# Git_USB_Hub.net
KiCad netlist of a schematic drawn in EasyEDA Pro
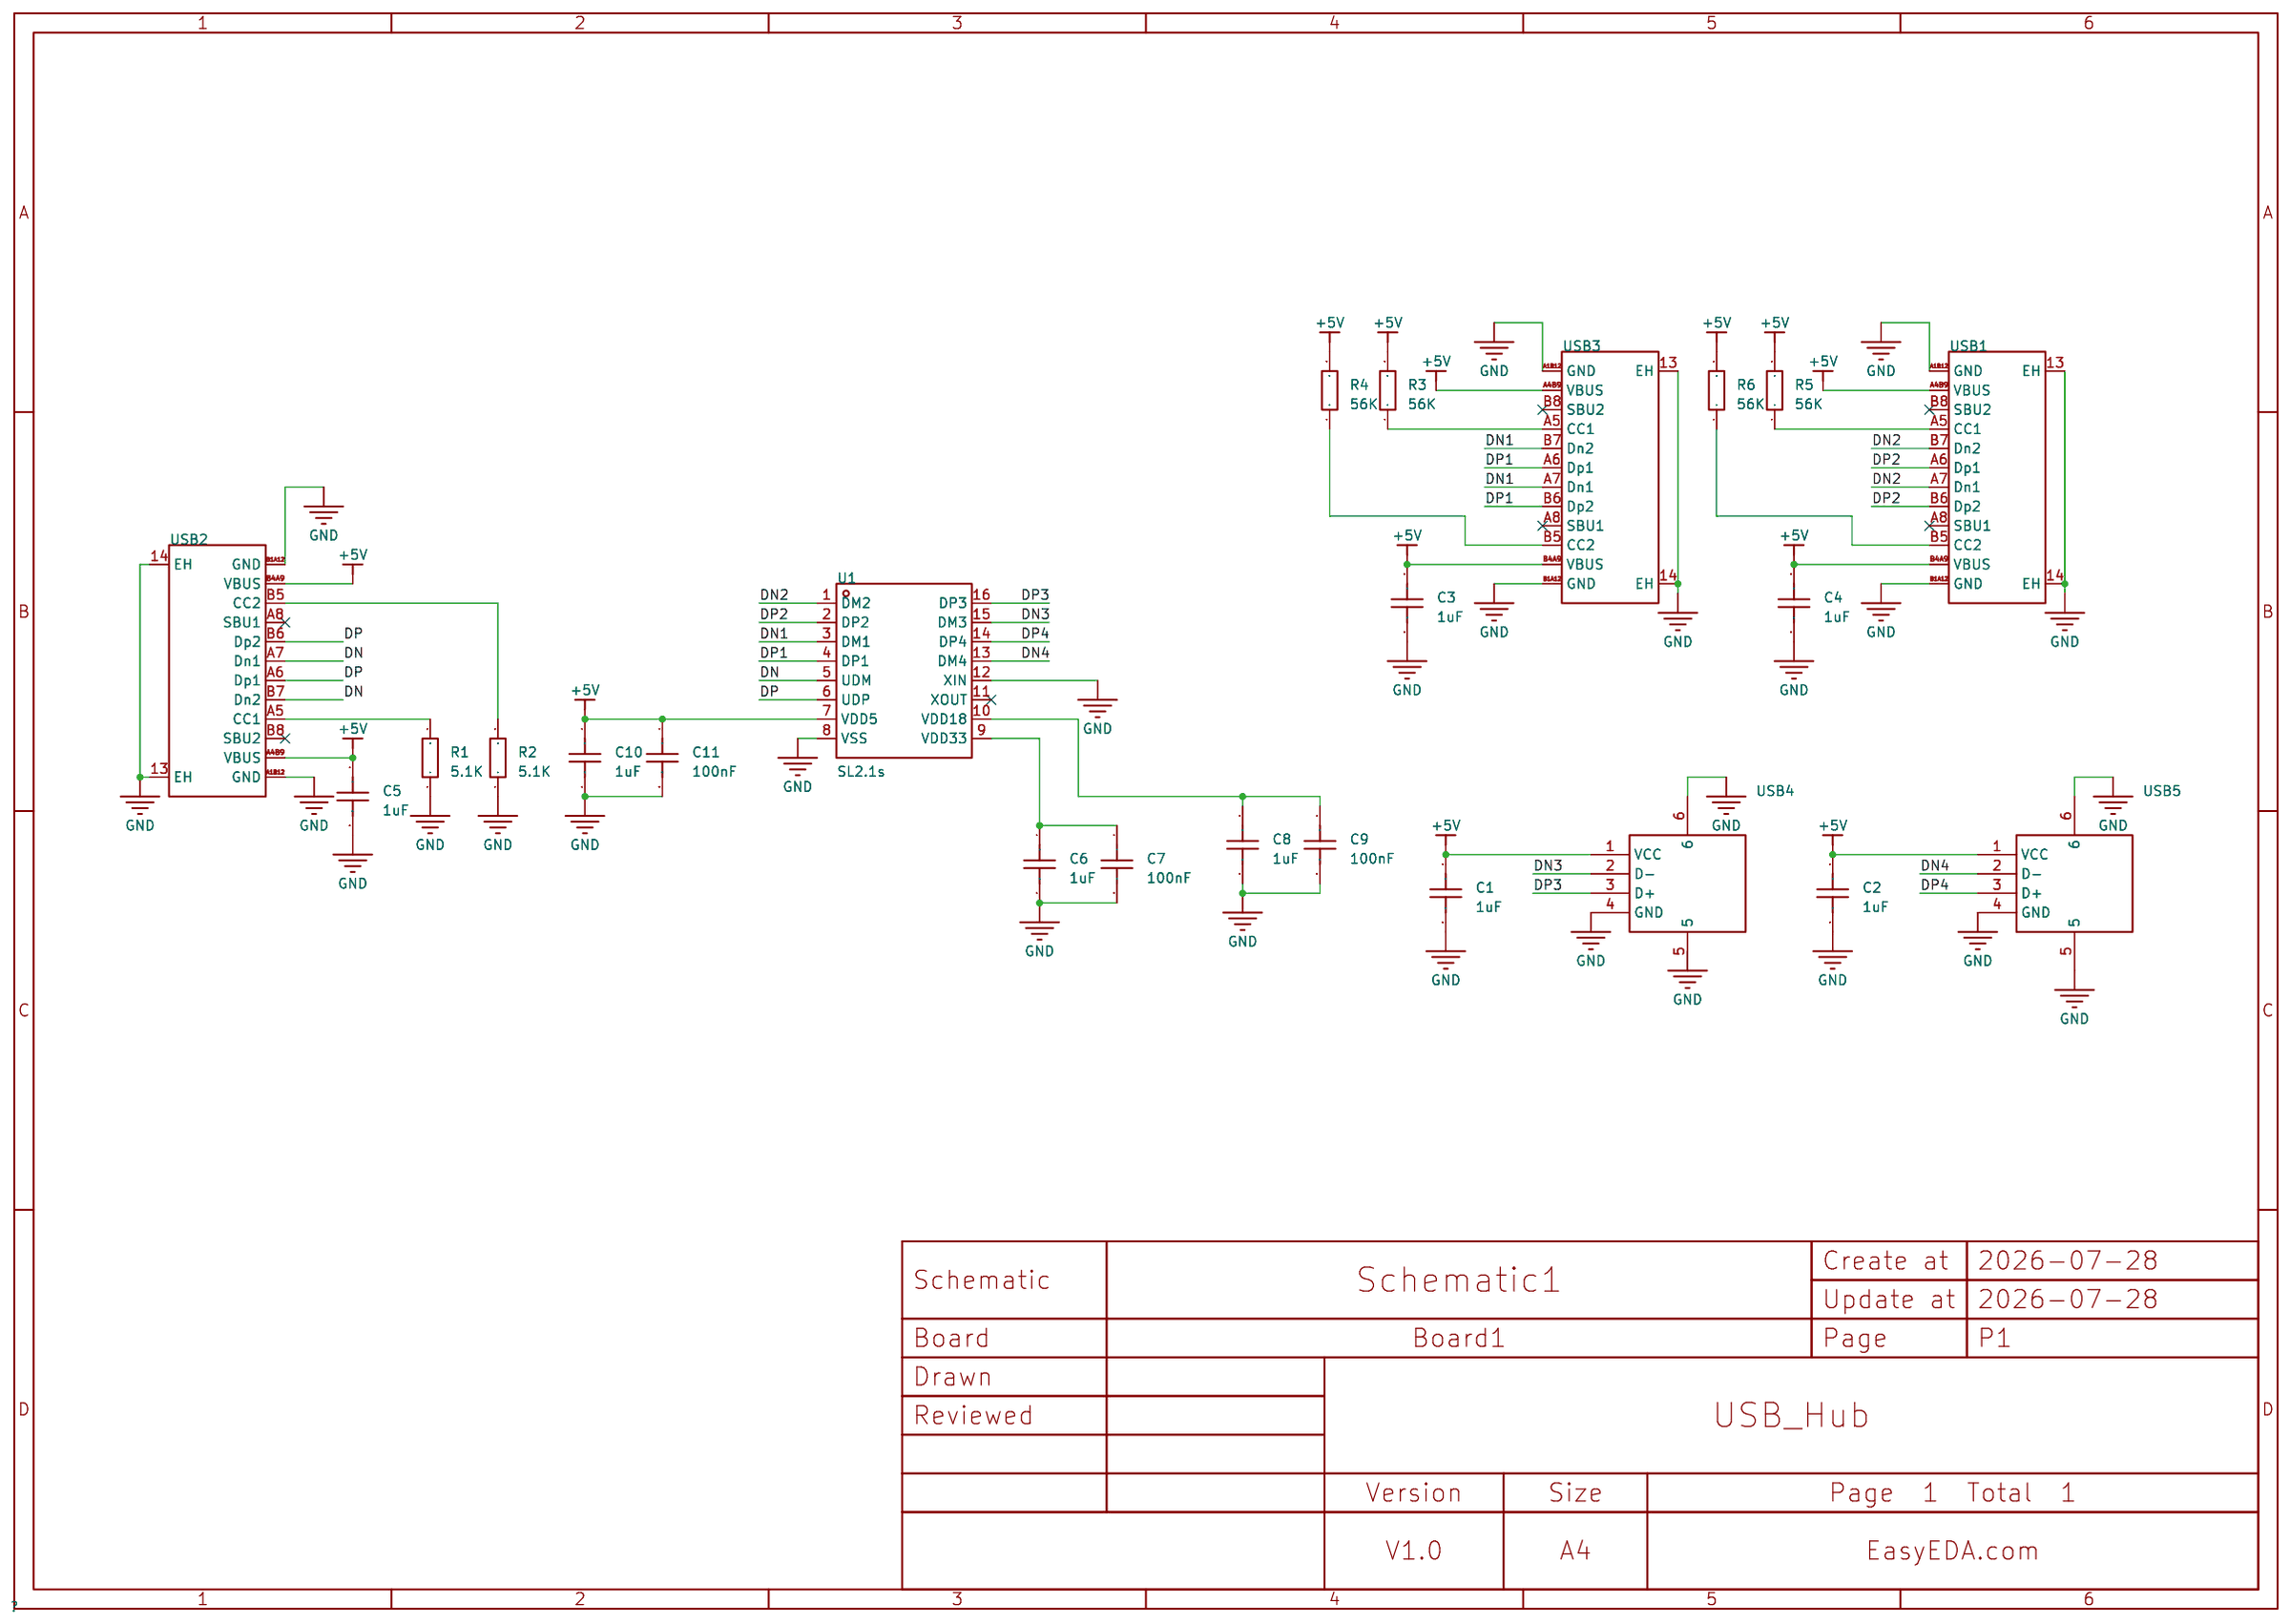
[diagram p0: schematic sheet]

(export (version "E")
  (design (tool "Eeschema 10.0.6"))
  (components
    (comp (ref "C1")
      (value "1uF")
      (footprint "easyedapro:C0603")
      (libsource (lib "easyedapro") (part "CAP_OLD"))
    )
    (comp (ref "C2")
      (value "1uF")
      (footprint "easyedapro:C0603")
      (libsource (lib "easyedapro") (part "CAP_OLD"))
    )
    (comp (ref "C3")
      (value "1uF")
      (footprint "easyedapro:C0603")
      (libsource (lib "easyedapro") (part "CAP_OLD"))
    )
    (comp (ref "C4")
      (value "1uF")
      (footprint "easyedapro:C0603")
      (libsource (lib "easyedapro") (part "CAP_OLD"))
    )
    (comp (ref "C5")
      (value "1uF")
      (footprint "easyedapro:C0603")
      (libsource (lib "easyedapro") (part "CAP_OLD"))
    )
    (comp (ref "C6")
      (value "1uF")
      (footprint "easyedapro:C0603")
      (libsource (lib "easyedapro") (part "CAP_OLD"))
    )
    (comp (ref "C7")
      (value "100nF")
      (footprint "easyedapro:C0603")
      (libsource (lib "easyedapro") (part "CAP_OLD"))
    )
    (comp (ref "C8")
      (value "1uF")
      (footprint "easyedapro:C0603")
      (libsource (lib "easyedapro") (part "CAP_OLD"))
    )
    (comp (ref "C9")
      (value "100nF")
      (footprint "easyedapro:C0603")
      (libsource (lib "easyedapro") (part "CAP_OLD"))
    )
    (comp (ref "C10")
      (value "1uF")
      (footprint "easyedapro:C0603")
      (libsource (lib "easyedapro") (part "CAP_OLD"))
    )
    (comp (ref "C11")
      (value "100nF")
      (footprint "easyedapro:C0603")
      (libsource (lib "easyedapro") (part "CAP_OLD"))
    )
    (comp (ref "R1")
      (value "5.1K")
      (footprint "easyedapro:R0603")
      (libsource (lib "easyedapro") (part "Res"))
    )
    (comp (ref "R2")
      (value "5.1K")
      (footprint "easyedapro:R0603")
      (libsource (lib "easyedapro") (part "Res"))
    )
    (comp (ref "R3") (value "56K") (footprint "easyedapro:R0603") (libsource (lib "easyedapro") (part "Res")))
    (comp (ref "R4") (value "56K") (footprint "easyedapro:R0603") (libsource (lib "easyedapro") (part "Res")))
    (comp (ref "R5") (value "56K") (footprint "easyedapro:R0603") (libsource (lib "easyedapro") (part "Res")))
    (comp (ref "R6") (value "56K") (footprint "easyedapro:R0603") (libsource (lib "easyedapro") (part "Res")))
    (comp (ref "U1")
      (value "SL2.1s")
      (footprint "easyedapro:SSOP-16_L4.6-W2.6-P0.53-LS4.0-BL")
      (fields (field (name "Manufacturer") "CoreChips(和芯润德)"))
      (libsource (lib "easyedapro") (part "SL2.1S"))
    )
    (comp (ref "USB1")
      (value "TYPE-C 16PIN 2MD(073)")
      (footprint "easyedapro:USB-C-SMD_TYPE-C-16PIN-2MD-073")
      (fields (field (name "Manufacturer") "SHOU HAN(首韩)"))
      (libsource (lib "easyedapro") (part "TYPE-C 16PIN 2MD(073)"))
    )
    (comp (ref "USB2")
      (value "TYPE-C 16PIN 2MD(073)")
      (footprint "easyedapro:USB-C-SMD_TYPE-C-16PIN-2MD-073")
      (fields (field (name "Manufacturer") "SHOU HAN(首韩)"))
      (libsource (lib "easyedapro") (part "TYPE-C 16PIN 2MD(073)"))
    )
    (comp (ref "USB3")
      (value "TYPE-C 16PIN 2MD(073)")
      (footprint "easyedapro:USB-C-SMD_TYPE-C-16PIN-2MD-073")
      (fields (field (name "Manufacturer") "SHOU HAN(首韩)"))
      (libsource (lib "easyedapro") (part "TYPE-C 16PIN 2MD(073)"))
    )
    (comp (ref "USB4")
      (value "10.0 QHHTZB6.3")
      (footprint "easyedapro:USB-A-TH_10.0QHHTZB6.3")
      (fields (field (name "Manufacturer") "SHOU HAN(首韩)"))
      (libsource (lib "easyedapro") (part "10.0 QHHTZB6.3"))
    )
    (comp (ref "USB5")
      (value "10.0 QHHTZB6.3")
      (footprint "easyedapro:USB-A-TH_10.0QHHTZB6.3")
      (fields (field (name "Manufacturer") "SHOU HAN(首韩)"))
      (libsource (lib "easyedapro") (part "10.0 QHHTZB6.3"))
    )
  )
  (nets
    (net (code "1") (name "+5V") (class "Default")
      (node (ref "C1") (pin "1") (pinfunction "1_1") (pintype "input"))
      (node (ref "C10") (pin "1") (pinfunction "1_1") (pintype "input"))
      (node (ref "C11") (pin "1") (pinfunction "1_1") (pintype "input"))
      (node (ref "C2") (pin "1") (pinfunction "1_1") (pintype "input"))
      (node (ref "C3") (pin "1") (pinfunction "1_1") (pintype "input"))
      (node (ref "C4") (pin "1") (pinfunction "1_1") (pintype "input"))
      (node (ref "C5") (pin "1") (pinfunction "1_1") (pintype "input"))
      (node (ref "R3") (pin "2") (pinfunction "2_2") (pintype "input"))
      (node (ref "R4") (pin "2") (pinfunction "2_2") (pintype "input"))
      (node (ref "R5") (pin "2") (pinfunction "2_2") (pintype "input"))
      (node (ref "R6") (pin "2") (pinfunction "2_2") (pintype "input"))
      (node (ref "U1") (pin "7") (pinfunction "VDD5_7") (pintype "unspecified"))
      (node (ref "USB1") (pin "A4B9") (pinfunction "VBUS_A4B9") (pintype "unspecified"))
      (node (ref "USB1") (pin "B4A9") (pinfunction "VBUS_B4A9") (pintype "unspecified"))
      (node (ref "USB2") (pin "A4B9") (pinfunction "VBUS_A4B9") (pintype "unspecified"))
      (node (ref "USB2") (pin "B4A9") (pinfunction "VBUS_B4A9") (pintype "unspecified"))
      (node (ref "USB3") (pin "A4B9") (pinfunction "VBUS_A4B9") (pintype "unspecified"))
      (node (ref "USB3") (pin "B4A9") (pinfunction "VBUS_B4A9") (pintype "unspecified"))
      (node (ref "USB4") (pin "1") (pinfunction "VCC_1") (pintype "unspecified"))
      (node (ref "USB5") (pin "1") (pinfunction "VCC_1") (pintype "unspecified"))
    )
    (net (code "2") (name "/DN") (class "Default")
      (node (ref "U1") (pin "5") (pinfunction "UDM_5") (pintype "unspecified"))
      (node (ref "USB2") (pin "A7") (pinfunction "Dn1_A7") (pintype "unspecified"))
      (node (ref "USB2") (pin "B7") (pinfunction "Dn2_B7") (pintype "unspecified"))
    )
    (net (code "3") (name "/DN1") (class "Default")
      (node (ref "U1") (pin "3") (pinfunction "DM1_3") (pintype "unspecified"))
      (node (ref "USB3") (pin "A7") (pinfunction "Dn1_A7") (pintype "unspecified"))
      (node (ref "USB3") (pin "B7") (pinfunction "Dn2_B7") (pintype "unspecified"))
    )
    (net (code "4") (name "/DN2") (class "Default")
      (node (ref "U1") (pin "1") (pinfunction "DM2_1") (pintype "unspecified"))
      (node (ref "USB1") (pin "A7") (pinfunction "Dn1_A7") (pintype "unspecified"))
      (node (ref "USB1") (pin "B7") (pinfunction "Dn2_B7") (pintype "unspecified"))
    )
    (net (code "5") (name "/DN3") (class "Default")
      (node (ref "U1") (pin "15") (pinfunction "DM3_15") (pintype "unspecified"))
      (node (ref "USB4") (pin "2") (pinfunction "D-_2") (pintype "unspecified"))
    )
    (net (code "6") (name "/DN4") (class "Default")
      (node (ref "U1") (pin "13") (pinfunction "DM4_13") (pintype "unspecified"))
      (node (ref "USB5") (pin "2") (pinfunction "D-_2") (pintype "unspecified"))
    )
    (net (code "7") (name "/DP") (class "Default")
      (node (ref "U1") (pin "6") (pinfunction "UDP_6") (pintype "unspecified"))
      (node (ref "USB2") (pin "A6") (pinfunction "Dp1_A6") (pintype "unspecified"))
      (node (ref "USB2") (pin "B6") (pinfunction "Dp2_B6") (pintype "unspecified"))
    )
    (net (code "8") (name "/DP1") (class "Default")
      (node (ref "U1") (pin "4") (pinfunction "DP1_4") (pintype "unspecified"))
      (node (ref "USB3") (pin "A6") (pinfunction "Dp1_A6") (pintype "unspecified"))
      (node (ref "USB3") (pin "B6") (pinfunction "Dp2_B6") (pintype "unspecified"))
    )
    (net (code "9") (name "/DP2") (class "Default")
      (node (ref "U1") (pin "2") (pinfunction "DP2_2") (pintype "unspecified"))
      (node (ref "USB1") (pin "A6") (pinfunction "Dp1_A6") (pintype "unspecified"))
      (node (ref "USB1") (pin "B6") (pinfunction "Dp2_B6") (pintype "unspecified"))
    )
    (net (code "10") (name "/DP3") (class "Default")
      (node (ref "U1") (pin "16") (pinfunction "DP3_16") (pintype "unspecified"))
      (node (ref "USB4") (pin "3") (pinfunction "D+_3") (pintype "unspecified"))
    )
    (net (code "11") (name "/DP4") (class "Default")
      (node (ref "U1") (pin "14") (pinfunction "DP4_14") (pintype "unspecified"))
      (node (ref "USB5") (pin "3") (pinfunction "D+_3") (pintype "unspecified"))
    )
    (net (code "12") (name "GND") (class "Default")
      (node (ref "C1") (pin "2") (pinfunction "2_2") (pintype "input"))
      (node (ref "C10") (pin "2") (pinfunction "2_2") (pintype "input"))
      (node (ref "C11") (pin "2") (pinfunction "2_2") (pintype "input"))
      (node (ref "C2") (pin "2") (pinfunction "2_2") (pintype "input"))
      (node (ref "C3") (pin "2") (pinfunction "2_2") (pintype "input"))
      (node (ref "C4") (pin "2") (pinfunction "2_2") (pintype "input"))
      (node (ref "C5") (pin "2") (pinfunction "2_2") (pintype "input"))
      (node (ref "C6") (pin "2") (pinfunction "2_2") (pintype "input"))
      (node (ref "C7") (pin "2") (pinfunction "2_2") (pintype "input"))
      (node (ref "C8") (pin "2") (pinfunction "2_2") (pintype "input"))
      (node (ref "C9") (pin "2") (pinfunction "2_2") (pintype "input"))
      (node (ref "R1") (pin "1") (pinfunction "1_1") (pintype "input"))
      (node (ref "R2") (pin "1") (pinfunction "1_1") (pintype "input"))
      (node (ref "U1") (pin "12") (pinfunction "XIN_12") (pintype "unspecified"))
      (node (ref "U1") (pin "8") (pinfunction "VSS_8") (pintype "unspecified"))
      (node (ref "USB1") (pin "13") (pinfunction "EH_13") (pintype "unspecified"))
      (node (ref "USB1") (pin "14") (pinfunction "EH_14") (pintype "unspecified"))
      (node (ref "USB1") (pin "A1B12") (pinfunction "GND_A1B12") (pintype "unspecified"))
      (node (ref "USB1") (pin "B1A12") (pinfunction "GND_B1A12") (pintype "unspecified"))
      (node (ref "USB2") (pin "13") (pinfunction "EH_13") (pintype "unspecified"))
      (node (ref "USB2") (pin "14") (pinfunction "EH_14") (pintype "unspecified"))
      (node (ref "USB2") (pin "A1B12") (pinfunction "GND_A1B12") (pintype "unspecified"))
      (node (ref "USB2") (pin "B1A12") (pinfunction "GND_B1A12") (pintype "unspecified"))
      (node (ref "USB3") (pin "13") (pinfunction "EH_13") (pintype "unspecified"))
      (node (ref "USB3") (pin "14") (pinfunction "EH_14") (pintype "unspecified"))
      (node (ref "USB3") (pin "A1B12") (pinfunction "GND_A1B12") (pintype "unspecified"))
      (node (ref "USB3") (pin "B1A12") (pinfunction "GND_B1A12") (pintype "unspecified"))
      (node (ref "USB4") (pin "4") (pinfunction "GND_4") (pintype "unspecified"))
      (node (ref "USB4") (pin "5") (pinfunction "5_5") (pintype "unspecified"))
      (node (ref "USB4") (pin "6") (pinfunction "6_6") (pintype "unspecified"))
      (node (ref "USB5") (pin "4") (pinfunction "GND_4") (pintype "unspecified"))
      (node (ref "USB5") (pin "5") (pinfunction "5_5") (pintype "unspecified"))
      (node (ref "USB5") (pin "6") (pinfunction "6_6") (pintype "unspecified"))
    )
    (net (code "13") (name "Net-(U1-VDD18)") (class "Default")
      (node (ref "C8") (pin "1") (pinfunction "1_1") (pintype "input"))
      (node (ref "C9") (pin "1") (pinfunction "1_1") (pintype "input"))
      (node (ref "U1") (pin "10") (pinfunction "VDD18_10") (pintype "unspecified"))
    )
    (net (code "14") (name "Net-(U1-VDD33)") (class "Default")
      (node (ref "C6") (pin "1") (pinfunction "1_1") (pintype "input"))
      (node (ref "C7") (pin "1") (pinfunction "1_1") (pintype "input"))
      (node (ref "U1") (pin "9") (pinfunction "VDD33_9") (pintype "unspecified"))
    )
    (net (code "15") (name "Net-(USB1-CC1)") (class "Default")
      (node (ref "R5") (pin "1") (pinfunction "1_1") (pintype "input"))
      (node (ref "USB1") (pin "A5") (pinfunction "CC1_A5") (pintype "unspecified"))
    )
    (net (code "16") (name "Net-(USB1-CC2)") (class "Default")
      (node (ref "R6") (pin "1") (pinfunction "1_1") (pintype "input"))
      (node (ref "USB1") (pin "B5") (pinfunction "CC2_B5") (pintype "unspecified"))
    )
    (net (code "17") (name "Net-(USB2-CC1)") (class "Default")
      (node (ref "R1") (pin "2") (pinfunction "2_2") (pintype "input"))
      (node (ref "USB2") (pin "A5") (pinfunction "CC1_A5") (pintype "unspecified"))
    )
    (net (code "18") (name "Net-(USB2-CC2)") (class "Default")
      (node (ref "R2") (pin "2") (pinfunction "2_2") (pintype "input"))
      (node (ref "USB2") (pin "B5") (pinfunction "CC2_B5") (pintype "unspecified"))
    )
    (net (code "19") (name "Net-(USB3-CC1)") (class "Default")
      (node (ref "R3") (pin "1") (pinfunction "1_1") (pintype "input"))
      (node (ref "USB3") (pin "A5") (pinfunction "CC1_A5") (pintype "unspecified"))
    )
    (net (code "20") (name "Net-(USB3-CC2)") (class "Default")
      (node (ref "R4") (pin "1") (pinfunction "1_1") (pintype "input"))
      (node (ref "USB3") (pin "B5") (pinfunction "CC2_B5") (pintype "unspecified"))
    )
    (net (code "21") (name "unconnected-(U1-XOUT-Pad11)") (class "Default")
      (node (ref "U1") (pin "11") (pinfunction "XOUT_11") (pintype "unspecified+no_connect"))
    )
    (net (code "22") (name "unconnected-(USB1-SBU1-PadA8)") (class "Default")
      (node (ref "USB1") (pin "A8") (pinfunction "SBU1_A8") (pintype "unspecified+no_connect"))
    )
    (net (code "23") (name "unconnected-(USB1-SBU2-PadB8)") (class "Default")
      (node (ref "USB1") (pin "B8") (pinfunction "SBU2_B8") (pintype "unspecified+no_connect"))
    )
    (net (code "24") (name "unconnected-(USB2-SBU1-PadA8)") (class "Default")
      (node (ref "USB2") (pin "A8") (pinfunction "SBU1_A8") (pintype "unspecified+no_connect"))
    )
    (net (code "25") (name "unconnected-(USB2-SBU2-PadB8)") (class "Default")
      (node (ref "USB2") (pin "B8") (pinfunction "SBU2_B8") (pintype "unspecified+no_connect"))
    )
    (net (code "26") (name "unconnected-(USB3-SBU1-PadA8)") (class "Default")
      (node (ref "USB3") (pin "A8") (pinfunction "SBU1_A8") (pintype "unspecified+no_connect"))
    )
    (net (code "27") (name "unconnected-(USB3-SBU2-PadB8)") (class "Default")
      (node (ref "USB3") (pin "B8") (pinfunction "SBU2_B8") (pintype "unspecified+no_connect"))
    )
  )
)
